# MiKro-1_0-Rev-A.net
KiCad netlist of a schematic drawn in EAGLE
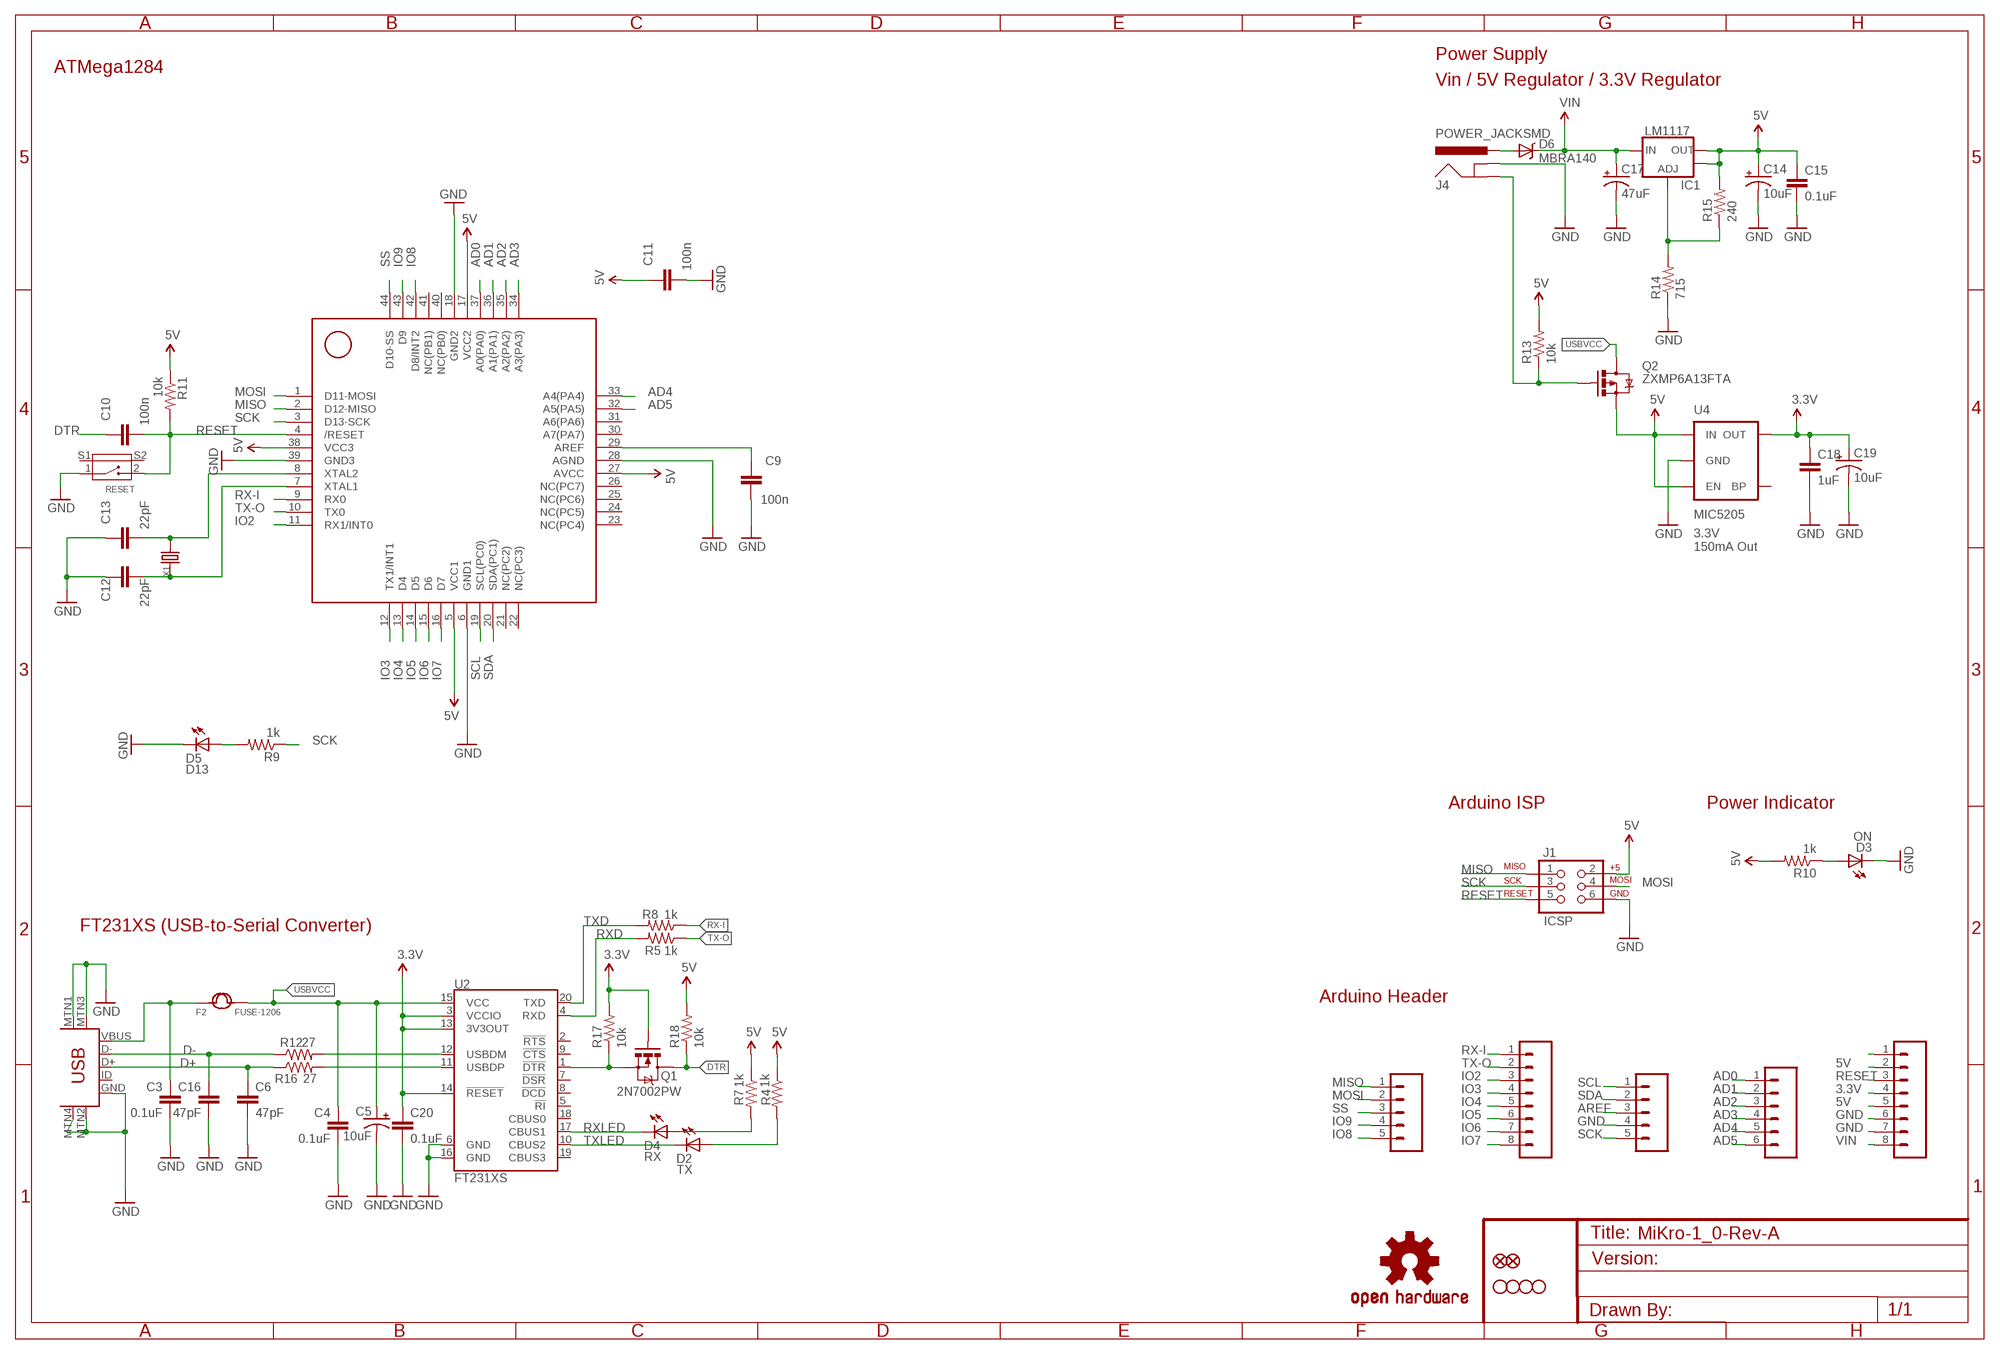
[diagram p0: schematic, sheet 1]

(export (version "E")
  (design (tool "Eeschema 10.0.6"))
  (components
    (comp (ref "C3")
      (value "0.1uF")
      (footprint "eagle-import:0603-CAP")
      (libsource (lib "eagle-import") (part "CAP0603-CAP"))
    )
    (comp (ref "C4")
      (value "0.1uF")
      (footprint "eagle-import:0603-CAP")
      (libsource (lib "eagle-import") (part "CAP0603-CAP"))
    )
    (comp (ref "C5")
      (value "10uF")
      (footprint "eagle-import:EIA3216")
      (libsource (lib "eagle-import") (part "SparkFun-Capacitors_CAP_POL1206"))
    )
    (comp (ref "C6")
      (value "47pF")
      (footprint "eagle-import:0603-CAP")
      (libsource (lib "eagle-import") (part "47PF-50V-5%(0603)"))
    )
    (comp (ref "C9")
      (value "100n")
      (footprint "eagle-import:0603-CAP")
      (libsource (lib "eagle-import") (part "SparkFun-Capacitors_CAP0603-CAP"))
    )
    (comp (ref "C10")
      (value "100n")
      (footprint "eagle-import:0603-CAP")
      (libsource (lib "eagle-import") (part "SparkFun-Capacitors_CAP0603-CAP"))
    )
    (comp (ref "C11")
      (value "100n")
      (footprint "eagle-import:0603-CAP")
      (libsource (lib "eagle-import") (part "SparkFun-Capacitors_CAP0603-CAP"))
    )
    (comp (ref "C12")
      (value "22pF")
      (footprint "eagle-import:0603-CAP")
      (libsource (lib "eagle-import") (part "SparkFun-Capacitors_CAP0603-CAP"))
    )
    (comp (ref "C13")
      (value "22pF")
      (footprint "eagle-import:0603-CAP")
      (libsource (lib "eagle-import") (part "SparkFun-Capacitors_CAP0603-CAP"))
    )
    (comp (ref "C14")
      (value "10uF")
      (footprint "eagle-import:EIA3216")
      (libsource (lib "eagle-import") (part "CAP_POL1206"))
    )
    (comp (ref "C15")
      (value "0.1uF")
      (footprint "eagle-import:0603-CAP")
      (libsource (lib "eagle-import") (part "CAP0603-CAP"))
    )
    (comp (ref "C16")
      (value "47pF")
      (footprint "eagle-import:0603-CAP")
      (libsource (lib "eagle-import") (part "47PF-50V-5%(0603)"))
    )
    (comp (ref "C17")
      (value "47uF")
      (footprint "eagle-import:PANASONIC_D")
      (libsource (lib "eagle-import") (part "CAP_POLD"))
    )
    (comp (ref "C18")
      (value "1uF")
      (footprint "eagle-import:0603-CAP")
      (libsource (lib "eagle-import") (part "CAP0603-CAP"))
    )
    (comp (ref "C19")
      (value "10uF")
      (footprint "eagle-import:EIA3216")
      (libsource (lib "eagle-import") (part "CAP_POL1206"))
    )
    (comp (ref "C20")
      (value "0.1uF")
      (footprint "eagle-import:0603-CAP")
      (libsource (lib "eagle-import") (part "CAP0603-CAP"))
    )
    (comp (ref "D2")
      (value "TX")
      (footprint "eagle-import:LED-0603")
      (libsource (lib "eagle-import") (part "LED0603"))
    )
    (comp (ref "D3")
      (value "ON")
      (footprint "eagle-import:LED-0603")
      (libsource (lib "eagle-import") (part "LED0603"))
    )
    (comp (ref "D4")
      (value "RX")
      (footprint "eagle-import:LED-0603")
      (libsource (lib "eagle-import") (part "LED0603"))
    )
    (comp (ref "D5")
      (value "D13")
      (footprint "eagle-import:LED-0603")
      (libsource (lib "eagle-import") (part "LED0603"))
    )
    (comp (ref "D6")
      (value "MBRA140")
      (footprint "eagle-import:SMA-DIODE")
      (libsource (lib "eagle-import") (part "DIODE-SCHOTTKY_"))
    )
    (comp (ref "F2")
      (value "FUSE-1206")
      (footprint "eagle-import:F1206")
      (libsource (lib "eagle-import") (part "FUSE-1206"))
    )
    (comp (ref "IC1")
      (value "LM1117")
      (footprint "eagle-import:SOT223-ALT1")
      (libsource (lib "eagle-import") (part "V_REG_LM1117ALT1"))
    )
    (comp (ref "J1")
      (value "ICSP")
      (footprint "eagle-import:2X3")
      (libsource (lib "eagle-import") (part "AVR_SPI_PRG_6PTH"))
    )
    (comp (ref "J4")
      (value "POWER_JACKSMD")
      (footprint "eagle-import:POWER_JACK_SMD")
      (libsource (lib "eagle-import") (part "POWER_JACKSMD"))
    )
    (comp (ref "JP1")
      (value "M08LONGPADS")
      (footprint "eagle-import:1X08_LONGPADS")
      (libsource (lib "eagle-import") (part "M08LONGPADS"))
    )
    (comp (ref "JP3")
      (value "STAND-OFF")
      (footprint "eagle-import:STAND-OFF")
      (libsource (lib "eagle-import") (part "STAND-OFF"))
    )
    (comp (ref "JP4")
      (value "STAND-OFF")
      (footprint "eagle-import:STAND-OFF")
      (libsource (lib "eagle-import") (part "STAND-OFF"))
    )
    (comp (ref "JP5")
      (value "STAND-OFF")
      (footprint "eagle-import:STAND-OFF")
      (libsource (lib "eagle-import") (part "STAND-OFF"))
    )
    (comp (ref "JP6")
      (value "STAND-OFF")
      (footprint "eagle-import:STAND-OFF")
      (libsource (lib "eagle-import") (part "STAND-OFF"))
    )
    (comp (ref "JP7")
      (value "M08LONGPADS")
      (footprint "eagle-import:1X08_LONGPADS")
      (libsource (lib "eagle-import") (part "M08LONGPADS"))
    )
    (comp (ref "JP8")
      (value "FIDUCIAL1X2")
      (footprint "eagle-import:FIDUCIAL-1X2")
      (libsource (lib "eagle-import") (part "FIDUCIAL1X2"))
    )
    (comp (ref "JP9")
      (value "FIDUCIAL1X2")
      (footprint "eagle-import:FIDUCIAL-1X2")
      (libsource (lib "eagle-import") (part "FIDUCIAL1X2"))
    )
    (comp (ref "JP11")
      (value "M06LONGPADS")
      (footprint "eagle-import:1X06_LONGPADS")
      (libsource (lib "eagle-import") (part "M06LONGPADS"))
    )
    (comp (ref "JP12")
      (value "M05PTH_LONGPADS")
      (footprint "eagle-import:1X05_LONGPADS")
      (libsource (lib "eagle-import") (part "M05PTH_LONGPADS"))
    )
    (comp (ref "JP13")
      (value "M05PTH_LONGPADS")
      (footprint "eagle-import:1X05_LONGPADS")
      (libsource (lib "eagle-import") (part "M05PTH_LONGPADS"))
    )
    (comp (ref "LOGO1")
      (value "OSHW-LOGOM")
      (footprint "eagle-import:OSHW-LOGO-M")
      (libsource (lib "eagle-import") (part "OSHW-LOGOM"))
    )
    (comp (ref "Q1")
      (value "2N7002PW")
      (footprint "eagle-import:SOT323")
      (libsource (lib "eagle-import") (part "MOSFET-NCHANNEL2N7002PW"))
    )
    (comp (ref "Q2")
      (value "ZXMP6A13FTA")
      (footprint "eagle-import:SOT23-3")
      (libsource (lib "eagle-import") (part "MOSFET-PCHANNELSMD"))
    )
    (comp (ref "R4")
      (value "1k")
      (footprint "eagle-import:0603-RES")
      (libsource (lib "eagle-import") (part "RESISTOR0603-RES"))
    )
    (comp (ref "R5")
      (value "1k")
      (footprint "eagle-import:0603-RES")
      (libsource (lib "eagle-import") (part "RESISTOR0603-RES"))
    )
    (comp (ref "R7")
      (value "1k")
      (footprint "eagle-import:0603-RES")
      (libsource (lib "eagle-import") (part "RESISTOR0603-RES"))
    )
    (comp (ref "R8")
      (value "1k")
      (footprint "eagle-import:0603-RES")
      (libsource (lib "eagle-import") (part "RESISTOR0603-RES"))
    )
    (comp (ref "R9")
      (value "1k")
      (footprint "eagle-import:0603-RES")
      (libsource (lib "eagle-import") (part "SparkFun-Resistors_RESISTOR0603-RES"))
    )
    (comp (ref "R10")
      (value "1k")
      (footprint "eagle-import:0603-RES")
      (libsource (lib "eagle-import") (part "SparkFun-Resistors_RESISTOR0603-RES"))
    )
    (comp (ref "R11")
      (value "10k")
      (footprint "eagle-import:0603-RES")
      (libsource (lib "eagle-import") (part "SparkFun-Resistors_RESISTOR0603-RES"))
    )
    (comp (ref "R12")
      (value "27")
      (footprint "eagle-import:0603-RES")
      (libsource (lib "eagle-import") (part "SparkFun-Resistors_RESISTOR0603-RES"))
    )
    (comp (ref "R13")
      (value "10k")
      (footprint "eagle-import:0603-RES")
      (libsource (lib "eagle-import") (part "RESISTOR0603-RES"))
    )
    (comp (ref "R14")
      (value "715")
      (footprint "eagle-import:0603-RES")
      (libsource (lib "eagle-import") (part "RESISTOR0603-RES"))
    )
    (comp (ref "R15")
      (value "240")
      (footprint "eagle-import:0603-RES")
      (libsource (lib "eagle-import") (part "RESISTOR0603-RES"))
    )
    (comp (ref "R16")
      (value "27")
      (footprint "eagle-import:0603-RES")
      (libsource (lib "eagle-import") (part "SparkFun-Resistors_RESISTOR0603-RES"))
    )
    (comp (ref "R17")
      (value "10k")
      (footprint "eagle-import:0603-RES")
      (libsource (lib "eagle-import") (part "RESISTOR0603-RES"))
    )
    (comp (ref "R18")
      (value "10k")
      (footprint "eagle-import:0603-RES")
      (libsource (lib "eagle-import") (part "RESISTOR0603-RES"))
    )
    (comp (ref "RESET")
      (value "BUTTON-2P-REINFORCE-3100060P1")
      (footprint "eagle-import:4P-SMD-7.0X3.5X3.5H-90D")
      (libsource (lib "eagle-import") (part "BUTTON-2P-REINFORCE-3100060P1"))
    )
    (comp (ref "U$3")
      (value "USB-MINIB-5PIN")
      (footprint "eagle-import:USB-MINIB")
      (libsource (lib "eagle-import") (part "USB-MINIB-5PIN"))
    )
    (comp (ref "U2")
      (value "FT231XS")
      (footprint "eagle-import:SSOP20_L")
      (libsource (lib "eagle-import") (part "FT231XS"))
    )
    (comp (ref "U3")
      (value "ATMEGA1284P")
      (footprint "eagle-import:TQFP44")
      (libsource (lib "eagle-import") (part "ATMEGA1284P"))
    )
    (comp (ref "U4")
      (value "MIC5205")
      (footprint "eagle-import:SOT23-5")
      (libsource (lib "eagle-import") (part "V_REG_LDOSMD"))
    )
    (comp (ref "X1")
      (value "CRYSTAL-0500290P1")
      (footprint "eagle-import:2P-SMD-5.0X3.2")
      (libsource (lib "eagle-import") (part "CRYSTAL-0500290P1"))
    )
  )
  (nets
    (net (code "1") (name "/AD0") (class "Default")
      (node (ref "JP11") (pin "1") (pinfunction "1_1") (pintype "passive"))
      (node (ref "U3") (pin "37") (pinfunction "A0(PA0)_37") (pintype "bidirectional"))
    )
    (net (code "2") (name "/AD1") (class "Default")
      (node (ref "JP11") (pin "2") (pinfunction "2_2") (pintype "passive"))
      (node (ref "U3") (pin "36") (pinfunction "A1(PA1)_36") (pintype "bidirectional"))
    )
    (net (code "3") (name "/AD2") (class "Default")
      (node (ref "JP11") (pin "3") (pinfunction "3_3") (pintype "passive"))
      (node (ref "U3") (pin "35") (pinfunction "A2(PA2)_35") (pintype "bidirectional"))
    )
    (net (code "4") (name "/AD3") (class "Default")
      (node (ref "JP11") (pin "4") (pinfunction "4_4") (pintype "passive"))
      (node (ref "U3") (pin "34") (pinfunction "A3(PA3)_34") (pintype "bidirectional"))
    )
    (net (code "5") (name "/AD4") (class "Default")
      (node (ref "JP11") (pin "5") (pinfunction "5_5") (pintype "passive"))
      (node (ref "U3") (pin "33") (pinfunction "A4(PA4)_33") (pintype "bidirectional"))
    )
    (net (code "6") (name "/AD5") (class "Default")
      (node (ref "JP11") (pin "6") (pinfunction "6_6") (pintype "passive"))
      (node (ref "U3") (pin "32") (pinfunction "A5(PA5)_32") (pintype "bidirectional"))
    )
    (net (code "7") (name "/AREF") (class "Default")
      (node (ref "JP12") (pin "3") (pinfunction "3_3") (pintype "passive"))
    )
    (net (code "8") (name "/D+") (class "Default")
      (node (ref "C6") (pin "1") (pinfunction "1_1") (pintype "passive"))
      (node (ref "R16") (pin "1") (pinfunction "1_1") (pintype "passive"))
      (node (ref "U$3") (pin "D+") (pinfunction "D+_D+") (pintype "bidirectional"))
    )
    (net (code "9") (name "/D-") (class "Default")
      (node (ref "C16") (pin "1") (pinfunction "1_1") (pintype "passive"))
      (node (ref "R12") (pin "1") (pinfunction "1_1") (pintype "passive"))
      (node (ref "U$3") (pin "D-") (pinfunction "D-_D-") (pintype "bidirectional"))
    )
    (net (code "10") (name "/IO2") (class "Default")
      (node (ref "JP1") (pin "3") (pinfunction "3_3") (pintype "passive"))
      (node (ref "U3") (pin "11") (pinfunction "RX1/INT0_11") (pintype "bidirectional"))
    )
    (net (code "11") (name "/IO3") (class "Default")
      (node (ref "JP1") (pin "4") (pinfunction "4_4") (pintype "passive"))
      (node (ref "U3") (pin "12") (pinfunction "TX1/INT1_12") (pintype "bidirectional"))
    )
    (net (code "12") (name "/IO4") (class "Default")
      (node (ref "JP1") (pin "5") (pinfunction "5_5") (pintype "passive"))
      (node (ref "U3") (pin "13") (pinfunction "D4_13") (pintype "bidirectional"))
    )
    (net (code "13") (name "/IO5") (class "Default")
      (node (ref "JP1") (pin "6") (pinfunction "6_6") (pintype "passive"))
      (node (ref "U3") (pin "14") (pinfunction "D5_14") (pintype "bidirectional"))
    )
    (net (code "14") (name "/IO6") (class "Default")
      (node (ref "JP1") (pin "7") (pinfunction "7_7") (pintype "passive"))
      (node (ref "U3") (pin "15") (pinfunction "D6_15") (pintype "bidirectional"))
    )
    (net (code "15") (name "/IO7") (class "Default")
      (node (ref "JP1") (pin "8") (pinfunction "8_8") (pintype "passive"))
      (node (ref "U3") (pin "16") (pinfunction "D7_16") (pintype "bidirectional"))
    )
    (net (code "16") (name "/IO8") (class "Default")
      (node (ref "JP13") (pin "5") (pinfunction "5_5") (pintype "passive"))
      (node (ref "U3") (pin "42") (pinfunction "D8/INT2_42") (pintype "bidirectional"))
    )
    (net (code "17") (name "/IO9") (class "Default")
      (node (ref "JP13") (pin "4") (pinfunction "4_4") (pintype "passive"))
      (node (ref "U3") (pin "43") (pinfunction "D9_43") (pintype "bidirectional"))
    )
    (net (code "18") (name "/MISO") (class "Default")
      (node (ref "J1") (pin "1") (pinfunction "1_1") (pintype "passive"))
      (node (ref "JP13") (pin "1") (pinfunction "1_1") (pintype "passive"))
      (node (ref "U3") (pin "2") (pinfunction "D12-MISO_2") (pintype "bidirectional"))
    )
    (net (code "19") (name "/MOSI") (class "Default")
      (node (ref "J1") (pin "4") (pinfunction "4_4") (pintype "passive"))
      (node (ref "JP13") (pin "2") (pinfunction "2_2") (pintype "passive"))
      (node (ref "U3") (pin "1") (pinfunction "D11-MOSI_1") (pintype "bidirectional"))
    )
    (net (code "20") (name "/RESET") (class "Default")
      (node (ref "C10") (pin "2") (pinfunction "2_2") (pintype "passive"))
      (node (ref "J1") (pin "5") (pinfunction "5_5") (pintype "passive"))
      (node (ref "JP7") (pin "3") (pinfunction "3_3") (pintype "passive"))
      (node (ref "R11") (pin "2") (pinfunction "2_2") (pintype "passive"))
      (node (ref "RESET") (pin "2") (pinfunction "2_2") (pintype "bidirectional"))
      (node (ref "U3") (pin "4") (pinfunction "/RESET_4") (pintype "bidirectional"))
    )
    (net (code "21") (name "/RXD") (class "Default")
      (node (ref "R5") (pin "2") (pinfunction "2_2") (pintype "passive"))
      (node (ref "U2") (pin "4") (pinfunction "RXD_4") (pintype "bidirectional"))
    )
    (net (code "22") (name "/RXLED") (class "Default")
      (node (ref "D4") (pin "C") (pinfunction "C_C") (pintype "passive"))
      (node (ref "U2") (pin "17") (pinfunction "CBUS1_17") (pintype "bidirectional"))
    )
    (net (code "23") (name "/SCK") (class "Default")
      (node (ref "J1") (pin "3") (pinfunction "3_3") (pintype "passive"))
      (node (ref "JP12") (pin "5") (pinfunction "5_5") (pintype "passive"))
      (node (ref "R9") (pin "1") (pinfunction "1_1") (pintype "passive"))
      (node (ref "U3") (pin "3") (pinfunction "D13-SCK_3") (pintype "bidirectional"))
    )
    (net (code "24") (name "/SCL") (class "Default")
      (node (ref "JP12") (pin "1") (pinfunction "1_1") (pintype "passive"))
      (node (ref "U3") (pin "19") (pinfunction "SCL(PC0)_19") (pintype "bidirectional"))
    )
    (net (code "25") (name "/SDA") (class "Default")
      (node (ref "JP12") (pin "2") (pinfunction "2_2") (pintype "passive"))
      (node (ref "U3") (pin "20") (pinfunction "SDA(PC1)_20") (pintype "bidirectional"))
    )
    (net (code "26") (name "/SS") (class "Default")
      (node (ref "JP13") (pin "3") (pinfunction "3_3") (pintype "passive"))
      (node (ref "U3") (pin "44") (pinfunction "D10-SS_44") (pintype "bidirectional"))
    )
    (net (code "27") (name "/TXD") (class "Default")
      (node (ref "R8") (pin "2") (pinfunction "2_2") (pintype "passive"))
      (node (ref "U2") (pin "20") (pinfunction "TXD_20") (pintype "bidirectional"))
    )
    (net (code "28") (name "/TXLED") (class "Default")
      (node (ref "D2") (pin "C") (pinfunction "C_C") (pintype "passive"))
      (node (ref "U2") (pin "10") (pinfunction "CBUS2_10") (pintype "bidirectional"))
    )
    (net (code "29") (name "3.3V") (class "Default")
      (node (ref "C18") (pin "1") (pinfunction "1_1") (pintype "passive"))
      (node (ref "C19") (pin "A") (pinfunction "+_A") (pintype "passive"))
      (node (ref "C20") (pin "1") (pinfunction "1_1") (pintype "passive"))
      (node (ref "JP7") (pin "4") (pinfunction "4_4") (pintype "passive"))
      (node (ref "Q1") (pin "1") (pinfunction "G_1") (pintype "passive"))
      (node (ref "R17") (pin "2") (pinfunction "2_2") (pintype "passive"))
      (node (ref "U2") (pin "13") (pinfunction "3V3OUT_13") (pintype "bidirectional"))
      (node (ref "U2") (pin "14") (pinfunction "~{RESET}_14") (pintype "bidirectional"))
      (node (ref "U2") (pin "3") (pinfunction "VCCIO_3") (pintype "bidirectional"))
      (node (ref "U4") (pin "5") (pinfunction "OUT_5") (pintype "passive"))
    )
    (net (code "30") (name "5V") (class "Default")
      (node (ref "C11") (pin "1") (pinfunction "1_1") (pintype "passive"))
      (node (ref "C14") (pin "A") (pinfunction "+_A") (pintype "passive"))
      (node (ref "C15") (pin "1") (pinfunction "1_1") (pintype "passive"))
      (node (ref "IC1") (pin "2") (pinfunction "OUT_2") (pintype "output"))
      (node (ref "IC1") (pin "4") (pinfunction "OUT_4") (pintype "output"))
      (node (ref "J1") (pin "2") (pinfunction "2_2") (pintype "passive"))
      (node (ref "JP7") (pin "2") (pinfunction "2_2") (pintype "passive"))
      (node (ref "JP7") (pin "5") (pinfunction "5_5") (pintype "passive"))
      (node (ref "Q2") (pin "2") (pinfunction "S_2") (pintype "passive"))
      (node (ref "R10") (pin "2") (pinfunction "2_2") (pintype "passive"))
      (node (ref "R11") (pin "1") (pinfunction "1_1") (pintype "passive"))
      (node (ref "R13") (pin "2") (pinfunction "2_2") (pintype "passive"))
      (node (ref "R15") (pin "2") (pinfunction "2_2") (pintype "passive"))
      (node (ref "R18") (pin "2") (pinfunction "2_2") (pintype "passive"))
      (node (ref "R4") (pin "1") (pinfunction "1_1") (pintype "passive"))
      (node (ref "R7") (pin "1") (pinfunction "1_1") (pintype "passive"))
      (node (ref "U3") (pin "17") (pinfunction "VCC2_17") (pintype "power_in"))
      (node (ref "U3") (pin "27") (pinfunction "AVCC_27") (pintype "power_in"))
      (node (ref "U3") (pin "38") (pinfunction "VCC3_38") (pintype "power_in"))
      (node (ref "U3") (pin "5") (pinfunction "VCC1_5") (pintype "power_in"))
      (node (ref "U4") (pin "1") (pinfunction "IN_1") (pintype "input"))
      (node (ref "U4") (pin "3") (pinfunction "EN_3") (pintype "input"))
    )
    (net (code "31") (name "DTR") (class "Default")
      (node (ref "C10") (pin "1") (pinfunction "1_1") (pintype "passive"))
      (node (ref "Q1") (pin "3") (pinfunction "D_3") (pintype "passive"))
      (node (ref "R18") (pin "1") (pinfunction "1_1") (pintype "passive"))
    )
    (net (code "32") (name "GND") (class "Default")
      (node (ref "C11") (pin "2") (pinfunction "2_2") (pintype "passive"))
      (node (ref "C12") (pin "1") (pinfunction "1_1") (pintype "passive"))
      (node (ref "C13") (pin "1") (pinfunction "1_1") (pintype "passive"))
      (node (ref "C14") (pin "C") (pinfunction "-_C") (pintype "passive"))
      (node (ref "C15") (pin "2") (pinfunction "2_2") (pintype "passive"))
      (node (ref "C16") (pin "2") (pinfunction "2_2") (pintype "passive"))
      (node (ref "C17") (pin "-") (pinfunction "-_-") (pintype "passive"))
      (node (ref "C18") (pin "2") (pinfunction "2_2") (pintype "passive"))
      (node (ref "C19") (pin "C") (pinfunction "-_C") (pintype "passive"))
      (node (ref "C20") (pin "2") (pinfunction "2_2") (pintype "passive"))
      (node (ref "C3") (pin "2") (pinfunction "2_2") (pintype "passive"))
      (node (ref "C4") (pin "2") (pinfunction "2_2") (pintype "passive"))
      (node (ref "C5") (pin "C") (pinfunction "-_C") (pintype "passive"))
      (node (ref "C6") (pin "2") (pinfunction "2_2") (pintype "passive"))
      (node (ref "C9") (pin "2") (pinfunction "2_2") (pintype "passive"))
      (node (ref "D3") (pin "C") (pinfunction "C_C") (pintype "passive"))
      (node (ref "D5") (pin "C") (pinfunction "C_C") (pintype "passive"))
      (node (ref "J1") (pin "6") (pinfunction "6_6") (pintype "passive"))
      (node (ref "J4") (pin "GND") (pinfunction "GNDBREAK_GND") (pintype "bidirectional"))
      (node (ref "JP12") (pin "4") (pinfunction "4_4") (pintype "passive"))
      (node (ref "JP7") (pin "6") (pinfunction "6_6") (pintype "passive"))
      (node (ref "JP7") (pin "7") (pinfunction "7_7") (pintype "passive"))
      (node (ref "R14") (pin "1") (pinfunction "1_1") (pintype "passive"))
      (node (ref "RESET") (pin "1") (pinfunction "1_1") (pintype "bidirectional"))
      (node (ref "U$3") (pin "GND") (pinfunction "GND_GND") (pintype "bidirectional"))
      (node (ref "U$3") (pin "MTN1") (pinfunction "MTN2_MTN1") (pintype "bidirectional"))
      (node (ref "U$3") (pin "MTN2") (pinfunction "MTN3_MTN2") (pintype "bidirectional"))
      (node (ref "U$3") (pin "MTN3") (pinfunction "MTN1_MTN3") (pintype "bidirectional"))
      (node (ref "U$3") (pin "MTN4") (pinfunction "MTN4_MTN4") (pintype "bidirectional"))
      (node (ref "U2") (pin "16") (pinfunction "GND_16") (pintype "bidirectional"))
      (node (ref "U2") (pin "6") (pinfunction "GND_6") (pintype "bidirectional"))
      (node (ref "U3") (pin "18") (pinfunction "GND2_18") (pintype "power_in"))
      (node (ref "U3") (pin "28") (pinfunction "AGND_28") (pintype "power_in"))
      (node (ref "U3") (pin "39") (pinfunction "GND3_39") (pintype "power_in"))
      (node (ref "U3") (pin "6") (pinfunction "GND1_6") (pintype "power_in"))
      (node (ref "U4") (pin "2") (pinfunction "GND_2") (pintype "input"))
    )
    (net (code "33") (name "Net-(C3-Pad1)") (class "Default")
      (node (ref "C3") (pin "1") (pinfunction "1_1") (pintype "passive"))
      (node (ref "F2") (pin "1") (pinfunction "1_1") (pintype "bidirectional"))
      (node (ref "U$3") (pin "VBUS") (pinfunction "VBUS_VBUS") (pintype "bidirectional"))
    )
    (net (code "34") (name "Net-(D2-PadA)") (class "Default")
      (node (ref "D2") (pin "A") (pinfunction "A_A") (pintype "passive"))
      (node (ref "R4") (pin "2") (pinfunction "2_2") (pintype "passive"))
    )
    (net (code "35") (name "Net-(D3-PadA)") (class "Default")
      (node (ref "D3") (pin "A") (pinfunction "A_A") (pintype "passive"))
      (node (ref "R10") (pin "1") (pinfunction "1_1") (pintype "passive"))
    )
    (net (code "36") (name "Net-(D4-PadA)") (class "Default")
      (node (ref "D4") (pin "A") (pinfunction "A_A") (pintype "passive"))
      (node (ref "R7") (pin "2") (pinfunction "2_2") (pintype "passive"))
    )
    (net (code "37") (name "Net-(D5-PadA)") (class "Default")
      (node (ref "D5") (pin "A") (pinfunction "A_A") (pintype "passive"))
      (node (ref "R9") (pin "2") (pinfunction "2_2") (pintype "passive"))
    )
    (net (code "38") (name "Net-(IC1-ADJ)") (class "Default")
      (node (ref "IC1") (pin "1") (pinfunction "ADJ_1") (pintype "input"))
      (node (ref "R14") (pin "2") (pinfunction "2_2") (pintype "passive"))
      (node (ref "R15") (pin "1") (pinfunction "1_1") (pintype "passive"))
    )
    (net (code "39") (name "Net-(J4-GND)") (class "Default")
      (node (ref "J4") (pin "P$4") (pinfunction "GND_P$4") (pintype "bidirectional"))
      (node (ref "Q2") (pin "1") (pinfunction "G_1") (pintype "passive"))
      (node (ref "R13") (pin "1") (pinfunction "1_1") (pintype "passive"))
    )
    (net (code "40") (name "Net-(J4-PWR)") (class "Default")
      (node (ref "D6") (pin "A") (pinfunction "A_A") (pintype "passive"))
      (node (ref "J4") (pin "VIN0") (pinfunction "PWR_VIN0") (pintype "bidirectional"))
    )
    (net (code "41") (name "Net-(Q1-S)") (class "Default")
      (node (ref "Q1") (pin "2") (pinfunction "S_2") (pintype "passive"))
      (node (ref "R17") (pin "1") (pinfunction "1_1") (pintype "passive"))
      (node (ref "U2") (pin "1") (pinfunction "~{DTR}_1") (pintype "bidirectional"))
    )
    (net (code "42") (name "Net-(U2-USBDM)") (class "Default")
      (node (ref "R12") (pin "2") (pinfunction "2_2") (pintype "passive"))
      (node (ref "U2") (pin "12") (pinfunction "USBDM_12") (pintype "bidirectional"))
    )
    (net (code "43") (name "Net-(U2-USBDP)") (class "Default")
      (node (ref "R16") (pin "2") (pinfunction "2_2") (pintype "passive"))
      (node (ref "U2") (pin "11") (pinfunction "USBDP_11") (pintype "bidirectional"))
    )
    (net (code "44") (name "Net-(U3-AREF)") (class "Default")
      (node (ref "C9") (pin "1") (pinfunction "1_1") (pintype "passive"))
      (node (ref "U3") (pin "29") (pinfunction "AREF_29") (pintype "bidirectional"))
    )
    (net (code "45") (name "Net-(U3-XTAL1)") (class "Default")
      (node (ref "C12") (pin "2") (pinfunction "2_2") (pintype "passive"))
      (node (ref "U3") (pin "7") (pinfunction "XTAL1_7") (pintype "bidirectional"))
      (node (ref "X1") (pin "1") (pinfunction "1_1") (pintype "passive"))
    )
    (net (code "46") (name "Net-(U3-XTAL2)") (class "Default")
      (node (ref "C13") (pin "2") (pinfunction "2_2") (pintype "passive"))
      (node (ref "U3") (pin "8") (pinfunction "XTAL2_8") (pintype "bidirectional"))
      (node (ref "X1") (pin "2") (pinfunction "2_2") (pintype "passive"))
    )
    (net (code "47") (name "RX-I") (class "Default")
      (node (ref "JP1") (pin "1") (pinfunction "1_1") (pintype "passive"))
      (node (ref "R8") (pin "1") (pinfunction "1_1") (pintype "passive"))
      (node (ref "U3") (pin "9") (pinfunction "RX0_9") (pintype "bidirectional"))
    )
    (net (code "48") (name "TX-O") (class "Default")
      (node (ref "JP1") (pin "2") (pinfunction "2_2") (pintype "passive"))
      (node (ref "R5") (pin "1") (pinfunction "1_1") (pintype "passive"))
      (node (ref "U3") (pin "10") (pinfunction "TX0_10") (pintype "bidirectional"))
    )
    (net (code "49") (name "USBVCC") (class "Default")
      (node (ref "C4") (pin "1") (pinfunction "1_1") (pintype "passive"))
      (node (ref "C5") (pin "A") (pinfunction "+_A") (pintype "passive"))
      (node (ref "F2") (pin "2") (pinfunction "2_2") (pintype "bidirectional"))
      (node (ref "Q2") (pin "3") (pinfunction "D_3") (pintype "passive"))
      (node (ref "U2") (pin "15") (pinfunction "VCC_15") (pintype "bidirectional"))
    )
    (net (code "50") (name "VIN") (class "Default")
      (node (ref "C17") (pin "+") (pinfunction "+_+") (pintype "passive"))
      (node (ref "D6") (pin "C") (pinfunction "C_C") (pintype "passive"))
      (node (ref "IC1") (pin "3") (pinfunction "IN_3") (pintype "input"))
      (node (ref "JP7") (pin "8") (pinfunction "8_8") (pintype "passive"))
    )
    (net (code "51") (name "unconnected-(JP7-Pad1)") (class "Default")
      (node (ref "JP7") (pin "1") (pinfunction "1_1") (pintype "passive"))
    )
    (net (code "52") (name "unconnected-(RESET-PadS1)") (class "Default")
      (node (ref "RESET") (pin "S1") (pinfunction "S1_S1") (pintype "bidirectional"))
    )
    (net (code "53") (name "unconnected-(RESET-PadS2)") (class "Default")
      (node (ref "RESET") (pin "S2") (pinfunction "S2_S2") (pintype "bidirectional"))
    )
    (net (code "54") (name "unconnected-(U$3-PadID)") (class "Default")
      (node (ref "U$3") (pin "ID") (pinfunction "ID_ID") (pintype "bidirectional"))
    )
    (net (code "55") (name "unconnected-(U2-CBUS0-Pad18)") (class "Default")
      (node (ref "U2") (pin "18") (pinfunction "CBUS0_18") (pintype "bidirectional"))
    )
    (net (code "56") (name "unconnected-(U2-CBUS3-Pad19)") (class "Default")
      (node (ref "U2") (pin "19") (pinfunction "CBUS3_19") (pintype "bidirectional"))
    )
    (net (code "57") (name "unconnected-(U2-~{CTS}-Pad9)") (class "Default")
      (node (ref "U2") (pin "9") (pinfunction "~{CTS}_9") (pintype "bidirectional"))
    )
    (net (code "58") (name "unconnected-(U2-~{DCD}-Pad8)") (class "Default")
      (node (ref "U2") (pin "8") (pinfunction "~{DCD}_8") (pintype "bidirectional"))
    )
    (net (code "59") (name "unconnected-(U2-~{DSR}-Pad7)") (class "Default")
      (node (ref "U2") (pin "7") (pinfunction "~{DSR}_7") (pintype "bidirectional"))
    )
    (net (code "60") (name "unconnected-(U2-~{RI}-Pad5)") (class "Default")
      (node (ref "U2") (pin "5") (pinfunction "~{RI}_5") (pintype "bidirectional"))
    )
    (net (code "61") (name "unconnected-(U2-~{RTS}-Pad2)") (class "Default")
      (node (ref "U2") (pin "2") (pinfunction "~{RTS}_2") (pintype "bidirectional"))
    )
    (net (code "62") (name "unconnected-(U3-A6(PA6)-Pad31)") (class "Default")
      (node (ref "U3") (pin "31") (pinfunction "A6(PA6)_31") (pintype "bidirectional"))
    )
    (net (code "63") (name "unconnected-(U3-A7(PA7)-Pad30)") (class "Default")
      (node (ref "U3") (pin "30") (pinfunction "A7(PA7)_30") (pintype "bidirectional"))
    )
    (net (code "64") (name "unconnected-(U3-NC(PB0)-Pad40)") (class "Default")
      (node (ref "U3") (pin "40") (pinfunction "NC(PB0)_40") (pintype "bidirectional"))
    )
    (net (code "65") (name "unconnected-(U3-NC(PB1)-Pad41)") (class "Default")
      (node (ref "U3") (pin "41") (pinfunction "NC(PB1)_41") (pintype "bidirectional"))
    )
    (net (code "66") (name "unconnected-(U3-NC(PC2)-Pad21)") (class "Default")
      (node (ref "U3") (pin "21") (pinfunction "NC(PC2)_21") (pintype "bidirectional"))
    )
    (net (code "67") (name "unconnected-(U3-NC(PC3)-Pad22)") (class "Default")
      (node (ref "U3") (pin "22") (pinfunction "NC(PC3)_22") (pintype "bidirectional"))
    )
    (net (code "68") (name "unconnected-(U3-NC(PC4)-Pad23)") (class "Default")
      (node (ref "U3") (pin "23") (pinfunction "NC(PC4)_23") (pintype "bidirectional"))
    )
    (net (code "69") (name "unconnected-(U3-NC(PC5)-Pad24)") (class "Default")
      (node (ref "U3") (pin "24") (pinfunction "NC(PC5)_24") (pintype "bidirectional"))
    )
    (net (code "70") (name "unconnected-(U3-NC(PC6)-Pad25)") (class "Default")
      (node (ref "U3") (pin "25") (pinfunction "NC(PC6)_25") (pintype "bidirectional"))
    )
    (net (code "71") (name "unconnected-(U3-NC(PC7)-Pad26)") (class "Default")
      (node (ref "U3") (pin "26") (pinfunction "NC(PC7)_26") (pintype "bidirectional"))
    )
    (net (code "72") (name "unconnected-(U4-BP-Pad4)") (class "Default")
      (node (ref "U4") (pin "4") (pinfunction "BP_4") (pintype "input"))
    )
  )
)
